# AdcPmodPsu.net
KiCad netlist of a schematic drawn in Altium Designer
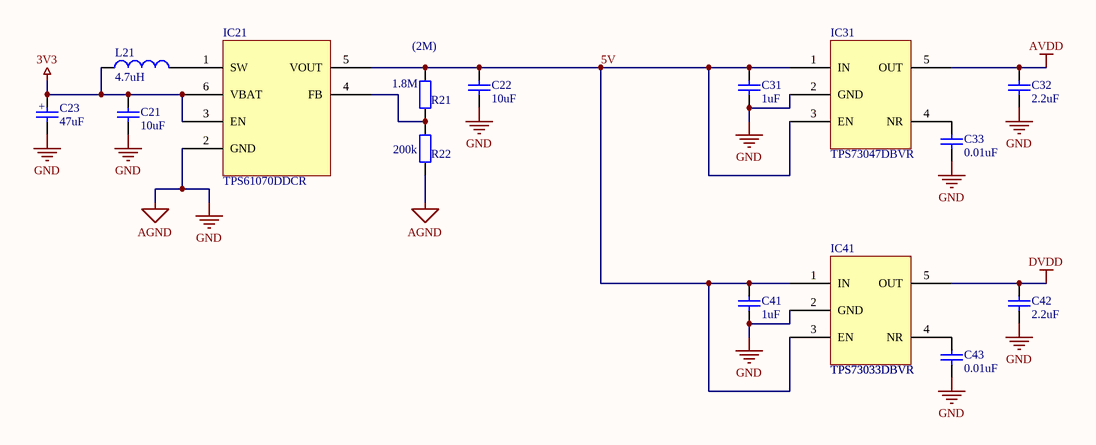
[diagram p0: AdcPmodPsu.SchDoc]

(export (version "E")
  (design (tool "Eeschema 10.0.6"))
  (components
    (comp (ref "C21")
      (value "10uF")
      (footprint "CAP0805")
      (description "Ceramic X7R")
      (fields
        (field (name "MANUFACTURER") "Murata Electronics")
        (field (name "MFR. PART NO.") "GRM21BR71A106KE51L")
      )
      (libsource (lib "AdcPmod") (part "CAP"))
    )
    (comp (ref "C22")
      (value "10uF")
      (footprint "CAP0805")
      (description "Ceramic X7R")
      (fields
        (field (name "MANUFACTURER") "Murata Electronics")
        (field (name "MFR. PART NO.") "GRM21BR71A106KE51L")
      )
      (libsource (lib "AdcPmod") (part "CAP"))
    )
    (comp (ref "C23")
      (value "47uF")
      (footprint "CAP_POL1206")
      (description "Capacitor Tantalum - Polymer")
      (fields
        (field (name "MANUFACTURER") "Vishay / Polytech")
        (field (name "MFR. PART NO.") "T58A0476M010C0100")
      )
      (libsource (lib "AdcPmod") (part "CAP_POL"))
    )
    (comp (ref "C31")
      (value "1uF")
      (footprint "CAP0805")
      (description "Ceramic X7R")
      (fields
        (field (name "MANUFACTURER") "Murata Electronics")
        (field (name "MFR. PART NO.") "GRM21BR71A105KA01L")
      )
      (libsource (lib "AdcPmod") (part "CAP"))
    )
    (comp (ref "C32")
      (value "2.2uF")
      (footprint "CAP0805")
      (description "Ceramic X7R")
      (fields
        (field (name "MANUFACTURER") "Murata Electronics")
        (field (name "MFR. PART NO.") "GRM21BR71A225KA01L")
      )
      (libsource (lib "AdcPmod") (part "CAP"))
    )
    (comp (ref "C33")
      (value "0.01uF")
      (footprint "CAP0805")
      (description "Ceramic X7R")
      (fields
        (field (name "MANUFACTURER") "Murata Electronics")
        (field (name "MFR. PART NO.") "GRM216R71E103KA01D")
      )
      (libsource (lib "AdcPmod") (part "CAP"))
    )
    (comp (ref "C41")
      (value "1uF")
      (footprint "CAP0805")
      (description "Ceramic X7R")
      (fields
        (field (name "MANUFACTURER") "Murata Electronics")
        (field (name "MFR. PART NO.") "GRM21BR71A105KA01L")
      )
      (libsource (lib "AdcPmod") (part "CAP"))
    )
    (comp (ref "C42")
      (value "2.2uF")
      (footprint "CAP0805")
      (description "Ceramic X7R")
      (fields
        (field (name "MANUFACTURER") "Murata Electronics")
        (field (name "MFR. PART NO.") "GRM21BR71A225KA01L")
      )
      (libsource (lib "AdcPmod") (part "CAP"))
    )
    (comp (ref "C43")
      (value "0.01uF")
      (footprint "CAP0805")
      (description "Ceramic X7R")
      (fields
        (field (name "MANUFACTURER") "Murata Electronics")
        (field (name "MFR. PART NO.") "GRM216R71E103KA01D")
      )
      (libsource (lib "AdcPmod") (part "CAP"))
    )
    (comp (ref "IC21")
      (value "TPS61070DDCR")
      (footprint "SOT23 (DDC TI)")
      (description "Adjustable, 600-mA Switch, 90% Efficient PFM/PWM Boost Converter")
      (fields
        (field (name "MANUFACTURER") "Texas Instruments")
        (field (name "MFR. PART NO.") "TPS61070DDCR")
        (field (name "SUPLIER PART NO.") "595-TPS61070DDCR")
      )
      (libsource (lib "AdcPmod") (part "TPS6107x"))
    )
    (comp (ref "IC31")
      (value "TPS73047DBVR")
      (footprint "SOT23 (5) (DBVTI)")
      (fields
        (field (name "MANUFACTURER") "Texas Instruments")
        (field (name "MFR. PART NO.") "TPS73047DBVR")
        (field (name "SUPLIER PART NO.") "595-TPS73047DBVR")
      )
      (libsource (lib "AdcPmod") (part "TPS730x"))
    )
    (comp (ref "IC41")
      (value "TPS73033DBVR")
      (footprint "SOT23 (5) (DBVTI)")
      (fields
        (field (name "MANUFACTURER") "Texas Instruments")
        (field (name "MFR. PART NO.") "TPS73033DBVR")
        (field (name "SUPLIER PART NO.") "595-TPS73033DBVT")
      )
      (libsource (lib "AdcPmod") (part "TPS730x"))
    )
    (comp (ref "L21")
      (value "4.7uH")
      (footprint "IND1206 (HS)")
      (description "Inductor")
      (fields
        (field (name "MANUFACTURER") "Murata Electronics")
        (field (name "MFR. PART NO.") "LQM31PN4R7M00L")
      )
      (libsource (lib "AdcPmod") (part "IND"))
    )
    (comp (ref "R21")
      (value "1.8M")
      (footprint "RES0805")
      (description "Thick Film")
      (fields (field (name "MANUFACTURER") "Vishay") (field (name "MFR. PART NO.") "CRCW12061M80FKEA"))
      (libsource (lib "AdcPmod") (part "RES"))
    )
    (comp (ref "R22")
      (value "200k")
      (footprint "RES0805")
      (description "Thin Film")
      (fields (field (name "MANUFACTURER") "Vishay") (field (name "MFR. PART NO.") "TNPW1206200KBEEA"))
      (libsource (lib "AdcPmod") (part "RES"))
    )
  )
  (nets
    (net (code "1") (name "/5V") (class "Default")
      (node (ref "C22") (pin "2") (pinfunction "2_2") (pintype "passive"))
      (node (ref "C31") (pin "2") (pinfunction "2_2") (pintype "passive"))
      (node (ref "C41") (pin "2") (pinfunction "2_2") (pintype "passive"))
      (node (ref "IC21") (pin "5") (pinfunction "VOUT_5") (pintype "passive"))
      (node (ref "IC31") (pin "1") (pinfunction "IN_1") (pintype "passive"))
      (node (ref "IC31") (pin "3") (pinfunction "EN_3") (pintype "passive"))
      (node (ref "IC41") (pin "1") (pinfunction "IN_1") (pintype "passive"))
      (node (ref "IC41") (pin "3") (pinfunction "EN_3") (pintype "passive"))
      (node (ref "R21") (pin "2") (pinfunction "2_2") (pintype "passive"))
    )
    (net (code "2") (name "3V3") (class "Default")
      (node (ref "C21") (pin "2") (pinfunction "2_2") (pintype "passive"))
      (node (ref "C23") (pin "1") (pinfunction "1_1") (pintype "passive"))
      (node (ref "IC21") (pin "3") (pinfunction "EN_3") (pintype "passive"))
      (node (ref "IC21") (pin "6") (pinfunction "VBAT_6") (pintype "passive"))
      (node (ref "L21") (pin "1") (pinfunction "1_1") (pintype "passive"))
    )
    (net (code "3") (name "AGND") (class "Default")
      (node (ref "C21") (pin "1") (pinfunction "1_1") (pintype "passive"))
      (node (ref "C22") (pin "1") (pinfunction "1_1") (pintype "passive"))
      (node (ref "C23") (pin "2") (pinfunction "2_2") (pintype "passive"))
      (node (ref "C31") (pin "1") (pinfunction "1_1") (pintype "passive"))
      (node (ref "C32") (pin "1") (pinfunction "1_1") (pintype "passive"))
      (node (ref "C33") (pin "1") (pinfunction "1_1") (pintype "passive"))
      (node (ref "C41") (pin "1") (pinfunction "1_1") (pintype "passive"))
      (node (ref "C42") (pin "1") (pinfunction "1_1") (pintype "passive"))
      (node (ref "C43") (pin "1") (pinfunction "1_1") (pintype "passive"))
      (node (ref "IC21") (pin "2") (pinfunction "GND_2") (pintype "passive"))
      (node (ref "IC31") (pin "2") (pinfunction "GND_2") (pintype "passive"))
      (node (ref "IC41") (pin "2") (pinfunction "GND_2") (pintype "passive"))
      (node (ref "R22") (pin "1") (pinfunction "1_1") (pintype "passive"))
    )
    (net (code "4") (name "AVDD") (class "Default")
      (node (ref "C32") (pin "2") (pinfunction "2_2") (pintype "passive"))
      (node (ref "IC31") (pin "5") (pinfunction "OUT_5") (pintype "passive"))
    )
    (net (code "5") (name "DVDD") (class "Default")
      (node (ref "C42") (pin "2") (pinfunction "2_2") (pintype "passive"))
      (node (ref "IC41") (pin "5") (pinfunction "OUT_5") (pintype "passive"))
    )
    (net (code "6") (name "Net-(IC21-FB)") (class "Default")
      (node (ref "IC21") (pin "4") (pinfunction "FB_4") (pintype "passive"))
      (node (ref "R21") (pin "1") (pinfunction "1_1") (pintype "passive"))
      (node (ref "R22") (pin "2") (pinfunction "2_2") (pintype "passive"))
    )
    (net (code "7") (name "Net-(IC21-SW)") (class "Default")
      (node (ref "IC21") (pin "1") (pinfunction "SW_1") (pintype "passive"))
      (node (ref "L21") (pin "2") (pinfunction "2_2") (pintype "passive"))
    )
    (net (code "8") (name "Net-(IC31-NR)") (class "Default")
      (node (ref "C33") (pin "2") (pinfunction "2_2") (pintype "passive"))
      (node (ref "IC31") (pin "4") (pinfunction "NR_4") (pintype "passive"))
    )
    (net (code "9") (name "Net-(IC41-NR)") (class "Default")
      (node (ref "C43") (pin "2") (pinfunction "2_2") (pintype "passive"))
      (node (ref "IC41") (pin "4") (pinfunction "NR_4") (pintype "passive"))
    )
  )
)
